# BATTERY_GESTION.net
KiCad netlist of a schematic drawn in Altium Designer
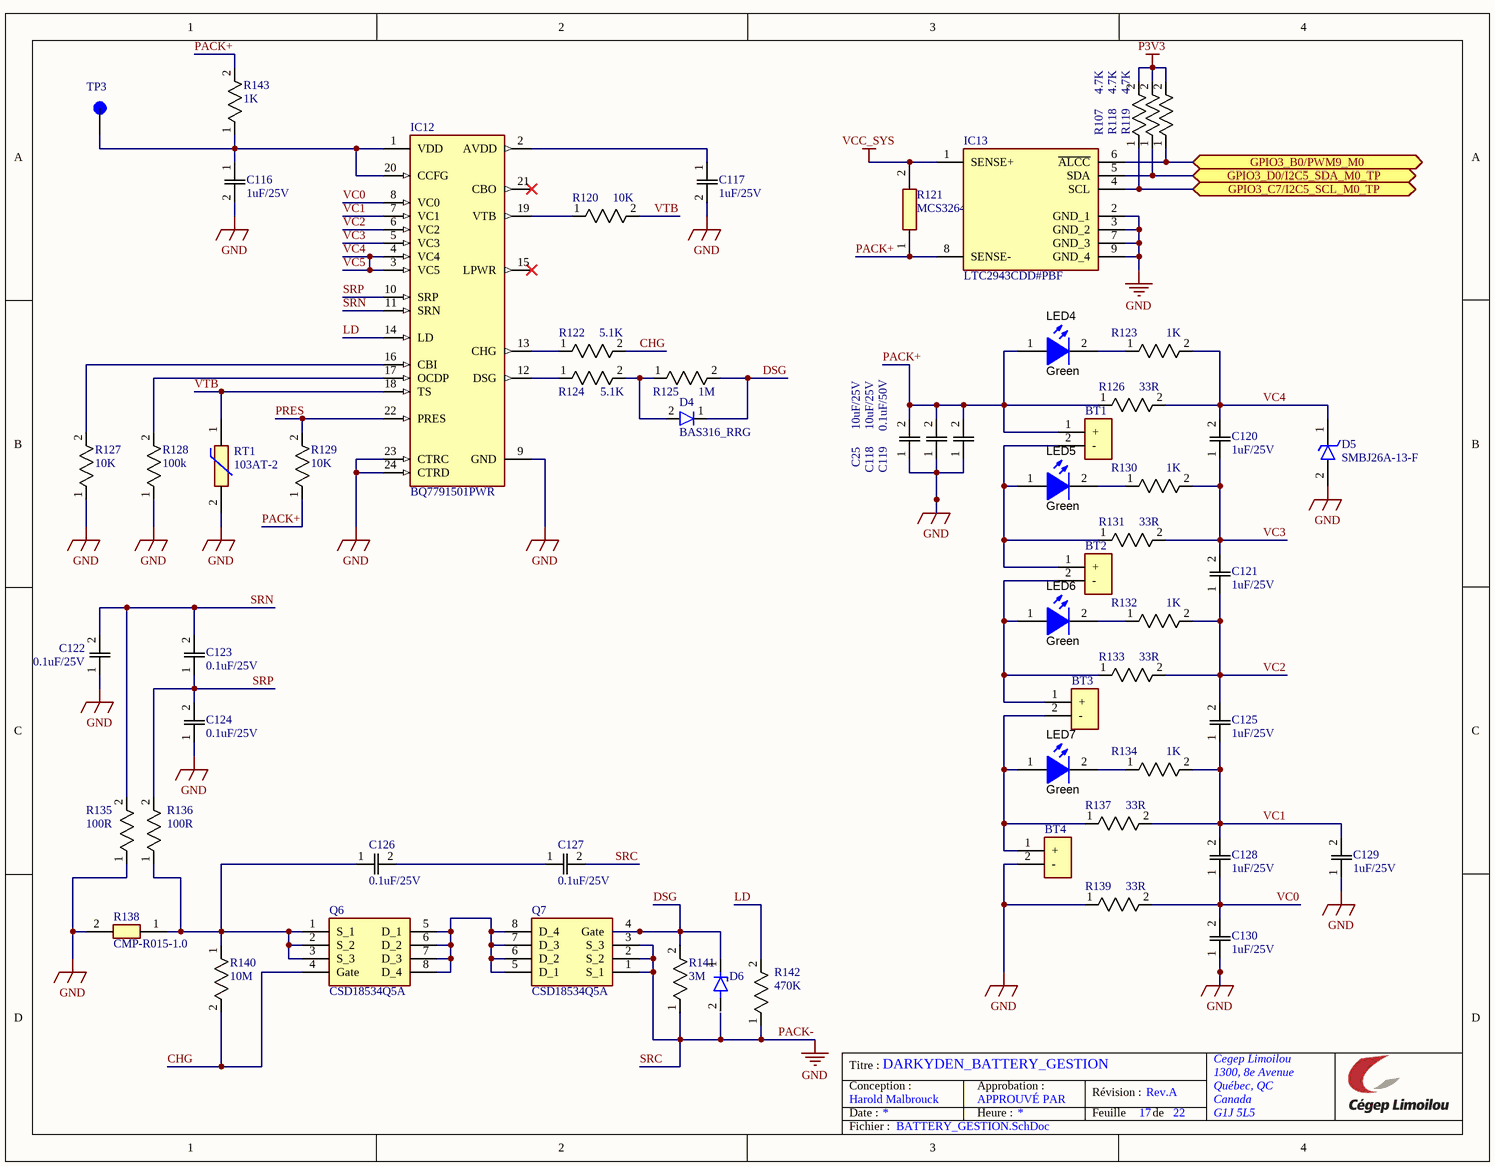
[diagram p0: BATTERY_GESTION.SchDoc]

(export (version "E")
  (design (tool "Eeschema 10.0.6"))
  (components
    (comp (ref "BT1")
      (value "0530480210")
      (footprint "SamacSys:SHDRRA2W35P0X125_1X2_425X550X350P")
      (description "Connector")
      (libsource (lib "SamacSys") (part "Header 1.25MM"))
    )
    (comp (ref "BT2")
      (value "0530480210")
      (footprint "SamacSys:SHDRRA2W35P0X125_1X2_425X550X350P")
      (description "Connector")
      (libsource (lib "SamacSys") (part "Header 1.25MM"))
    )
    (comp (ref "BT3")
      (value "0530480210")
      (footprint "SamacSys:SHDRRA2W35P0X125_1X2_425X550X350P")
      (description "Connector")
      (libsource (lib "SamacSys") (part "Header 1.25MM"))
    )
    (comp (ref "BT4")
      (value "0530480210")
      (footprint "SamacSys:SHDRRA2W35P0X125_1X2_425X550X350P")
      (description "Connector")
      (libsource (lib "SamacSys") (part "Header 1.25MM"))
    )
    (comp (ref "C25")
      (value "10uF/25V")
      (footprint "CAPC220145_88N_KEM")
      (description "10uF / 25 VDC, +85degC, X5R Dielec, +/-10% ¦ KEMET C0805C106K3PACTU 0805")
      (fields
        (field (name "MANUFACTURER") "KEMET")
        (field (name "MANUFACTURER PART NUMBER") "C0805C106K3PACTU")
      )
      (libsource (lib "C0805C106K3PACTU") (part "C0805C106K3PACTU"))
    )
    (comp (ref "C116")
      (value "1uF/25V")
      (footprint "SamacSys:C0805")
      (description "1 µF, 25 V (DC), ±10 %, SMD 0805, X7R, C0805C105K3RAC7800")
      (fields
        (field (name "MANUFACTURER_PART_NUMBER") "C0805C105K3RACTU")
        (field (name "MOUSER PART NUMBER") "80-C0805C105K3R")
      )
      (libsource (lib "SamacSys") (part "C0805C105K3RACTU"))
    )
    (comp (ref "C117")
      (value "1uF/25V")
      (footprint "SamacSys:C0805")
      (description "1 µF, 25 V (DC), ±10 %, SMD 0805, X7R, C0805C105K3RAC7800")
      (fields
        (field (name "MANUFACTURER_PART_NUMBER") "C0805C105K3RACTU")
        (field (name "MOUSER PART NUMBER") "80-C0805C105K3R")
      )
      (libsource (lib "SamacSys") (part "C0805C105K3RACTU"))
    )
    (comp (ref "C118")
      (value "10uF/25V")
      (footprint "CAPC220145_88N_KEM")
      (description "10uF / 25 VDC, +85degC, X5R Dielec, +/-10% ¦ KEMET C0805C106K3PACTU 0805")
      (fields
        (field (name "MANUFACTURER") "KEMET")
        (field (name "MANUFACTURER PART NUMBER") "C0805C106K3PACTU")
      )
      (libsource (lib "C0805C106K3PACTU") (part "C0805C106K3PACTU"))
    )
    (comp (ref "C119")
      (value "0.1uF/50V")
      (footprint "SamacSys:C0805")
      (description "0.1uF/50V X7R 10% 0805 Multilayer Ceramic Capacitors Mlcc Smd/Smt Rohs")
      (fields
        (field (name "MANUFACTURER_PART_NUMBER") "C0805C104K5RACTU")
        (field (name "MOUSER PART NUMBER") "80-C0805C104K5R")
      )
      (libsource (lib "SamacSys") (part "C0805C104K5RACTU"))
    )
    (comp (ref "C120")
      (value "1uF/25V")
      (footprint "SamacSys:C0805")
      (description "1 µF, 25 V (DC), ±10 %, SMD 0805, X7R, C0805C105K3RAC7800")
      (fields
        (field (name "MANUFACTURER_PART_NUMBER") "C0805C105K3RACTU")
        (field (name "MOUSER PART NUMBER") "80-C0805C105K3R")
      )
      (libsource (lib "SamacSys") (part "C0805C105K3RACTU"))
    )
    (comp (ref "C121")
      (value "1uF/25V")
      (footprint "SamacSys:C0805")
      (description "1 µF, 25 V (DC), ±10 %, SMD 0805, X7R, C0805C105K3RAC7800")
      (fields
        (field (name "MANUFACTURER_PART_NUMBER") "C0805C105K3RACTU")
        (field (name "MOUSER PART NUMBER") "80-C0805C105K3R")
      )
      (libsource (lib "SamacSys") (part "C0805C105K3RACTU"))
    )
    (comp (ref "C122")
      (value "0.1uF/25V")
      (footprint "CAPC220145_88N_KEM")
      (description "0.1uF 25V X7R 10% SMD 0805 125C Plastic T/R")
      (fields
        (field (name "MANUFACTURER") "KEMET")
        (field (name "MANUFACTURER PART NUMBER") "C0805C104K3RACTU")
      )
      (libsource (lib "C0805C104K3RACTU") (part "C0805C104K3RACTU"))
    )
    (comp (ref "C123")
      (value "0.1uF/25V")
      (footprint "CAPC220145_88N_KEM")
      (description "0.1uF 25V X7R 10% SMD 0805 125C Plastic T/R")
      (fields
        (field (name "MANUFACTURER") "KEMET")
        (field (name "MANUFACTURER PART NUMBER") "C0805C104K3RACTU")
      )
      (libsource (lib "C0805C104K3RACTU") (part "C0805C104K3RACTU"))
    )
    (comp (ref "C124")
      (value "0.1uF/25V")
      (footprint "CAPC220145_88N_KEM")
      (description "0.1uF 25V X7R 10% SMD 0805 125C Plastic T/R")
      (fields
        (field (name "MANUFACTURER") "KEMET")
        (field (name "MANUFACTURER PART NUMBER") "C0805C104K3RACTU")
      )
      (libsource (lib "C0805C104K3RACTU") (part "C0805C104K3RACTU"))
    )
    (comp (ref "C125")
      (value "1uF/25V")
      (footprint "SamacSys:C0805")
      (description "1 µF, 25 V (DC), ±10 %, SMD 0805, X7R, C0805C105K3RAC7800")
      (fields
        (field (name "MANUFACTURER_PART_NUMBER") "C0805C105K3RACTU")
        (field (name "MOUSER PART NUMBER") "80-C0805C105K3R")
      )
      (libsource (lib "SamacSys") (part "C0805C105K3RACTU"))
    )
    (comp (ref "C126")
      (value "0.1uF/25V")
      (footprint "CAPC220145_88N_KEM")
      (description "0.1uF 25V X7R 10% SMD 0805 125C Plastic T/R")
      (fields
        (field (name "MANUFACTURER") "KEMET")
        (field (name "MANUFACTURER PART NUMBER") "C0805C104K3RACTU")
      )
      (libsource (lib "C0805C104K3RACTU") (part "C0805C104K3RACTU"))
    )
    (comp (ref "C127")
      (value "0.1uF/25V")
      (footprint "CAPC220145_88N_KEM")
      (description "0.1uF 25V X7R 10% SMD 0805 125C Plastic T/R")
      (fields
        (field (name "MANUFACTURER") "KEMET")
        (field (name "MANUFACTURER PART NUMBER") "C0805C104K3RACTU")
      )
      (libsource (lib "C0805C104K3RACTU") (part "C0805C104K3RACTU"))
    )
    (comp (ref "C128")
      (value "1uF/25V")
      (footprint "SamacSys:C0805")
      (description "1 µF, 25 V (DC), ±10 %, SMD 0805, X7R, C0805C105K3RAC7800")
      (fields
        (field (name "MANUFACTURER_PART_NUMBER") "C0805C105K3RACTU")
        (field (name "MOUSER PART NUMBER") "80-C0805C105K3R")
      )
      (libsource (lib "SamacSys") (part "C0805C105K3RACTU"))
    )
    (comp (ref "C129")
      (value "1uF/25V")
      (footprint "SamacSys:C0805")
      (description "1 µF, 25 V (DC), ±10 %, SMD 0805, X7R, C0805C105K3RAC7800")
      (fields
        (field (name "MANUFACTURER_PART_NUMBER") "C0805C105K3RACTU")
        (field (name "MOUSER PART NUMBER") "80-C0805C105K3R")
      )
      (libsource (lib "SamacSys") (part "C0805C105K3RACTU"))
    )
    (comp (ref "C130")
      (value "1uF/25V")
      (footprint "SamacSys:C0805")
      (description "1 µF, 25 V (DC), ±10 %, SMD 0805, X7R, C0805C105K3RAC7800")
      (fields
        (field (name "MANUFACTURER_PART_NUMBER") "C0805C105K3RACTU")
        (field (name "MOUSER PART NUMBER") "80-C0805C105K3R")
      )
      (libsource (lib "SamacSys") (part "C0805C105K3RACTU"))
    )
    (comp (ref "D4")
      (value "BAS316_RRG")
      (footprint "SamacSys:BAS316RRG")
      (description "Rectifier Diode Small Signal Switching 0.25A 4ns 2-Pin SOD-323 T/R")
      (fields
        (field (name "MANUFACTURER_PART_NUMBER") "BAS316 RRG")
        (field (name "MOUSER PART NUMBER") "821-BAS316RRG")
      )
      (libsource (lib "SamacSys") (part "BAS316_RRG"))
    )
    (comp (ref "D5")
      (value "SMBJ26A-13-F")
      (footprint "SamacSys:DIOM5336X250N")
      (description "TVS DIODE 26VWM 42.1VC SMB")
      (fields (field (name "MOUSER PART NUMBER") "621-SMBJ26A-13-F"))
      (libsource (lib "SamacSys") (part "SMBJ26A-13-F"))
    )
    (comp (ref "D6")
      (value "MMSZ5248B-7-F")
      (footprint "SamacSys:SOD3716X115N")
      (description "Zener Diode 18 V 500 mW ±5% Surface Mount SOD-123")
      (libsource (lib "SamacSys") (part "MMSZ5248B-7-F"))
    )
    (comp (ref "IC12")
      (value "BQ7791501PWR")
      (footprint "SamacSys:SOP65P640X120-24N")
      (description "/Polymer 3~5 TSSOP-24 Battery Management ICs ROHS")
      (fields
        (field (name "MOUSER PART NUMBER") "595-BQ7791501PWR")
        (field (name "MANUFACTURER") "Texas Instruments")
      )
      (libsource (lib "SamacSys") (part "BQ7791501PWR"))
    )
    (comp (ref "IC13")
      (value "LTC2943CDD#PBF")
      (footprint "SamacSys:SON50P300X300X80-9N-D")
      (description "LTC2943 - Multicell Battery Gas Gauge with Temperature, Voltage and Current Measurement")
      (fields
        (field (name "MOUSER PART NUMBER") "584-LTC2943CDD#PBF")
        (field (name "MANUFACTURER") "Analog Devices / Linear Technology")
      )
      (libsource (lib "SamacSys") (part "LTC2943CDD#PBF"))
    )
    (comp (ref "LED4")
      (value "Green")
      (footprint "LED_LTST-C190")
      (description "LED, Green, SMD")
      (fields (field (name "MANUFACTURER") "Lite-On") (field (name "PARTNUMBER") "LTST-C190GKT"))
      (libsource (lib "PD_BQ_Ref_Design") (part "LED_Gr_SMD"))
    )
    (comp (ref "LED5")
      (value "Green")
      (footprint "LED_LTST-C190")
      (description "LED, Green, SMD")
      (fields (field (name "MANUFACTURER") "Lite-On") (field (name "PARTNUMBER") "LTST-C190GKT"))
      (libsource (lib "PD_BQ_Ref_Design") (part "LED_Gr_SMD"))
    )
    (comp (ref "LED6")
      (value "Green")
      (footprint "LED_LTST-C190")
      (description "LED, Green, SMD")
      (fields (field (name "MANUFACTURER") "Lite-On") (field (name "PARTNUMBER") "LTST-C190GKT"))
      (libsource (lib "PD_BQ_Ref_Design") (part "LED_Gr_SMD"))
    )
    (comp (ref "LED7")
      (value "Green")
      (footprint "LED_LTST-C190")
      (description "LED, Green, SMD")
      (fields (field (name "MANUFACTURER") "Lite-On") (field (name "PARTNUMBER") "LTST-C190GKT"))
      (libsource (lib "PD_BQ_Ref_Design") (part "LED_Gr_SMD"))
    )
    (comp (ref "Q6")
      (value "CSD18534Q5A")
      (footprint "SamacSys:Q5A")
      (description "MOSFET N-Channel 60 V 13A (Ta), 50A (Tc) 3.1W (Ta), 77W (Tc) Surface Mount 8-VSONP (5x6)")
      (fields (field (name "MOUSER PART NUMBER") "595-CSD18534Q5A"))
      (libsource (lib "SamacSys") (part "CSD18534Q5A"))
    )
    (comp (ref "Q7")
      (value "CSD18534Q5A")
      (footprint "SamacSys:Q5A")
      (description "MOSFET N-Channel 60 V 13A (Ta), 50A (Tc) 3.1W (Ta), 77W (Tc) Surface Mount 8-VSONP (5x6)")
      (fields (field (name "MOUSER PART NUMBER") "595-CSD18534Q5A"))
      (libsource (lib "") (part "CSD18534Q5A_1"))
    )
    (comp (ref "R107")
      (value "4.7K")
      (footprint "RC0603N_PAN")
      (description "Res Thin Film 0603 4.7K Ohm 0.1% 0.1W ±25ppm/°C Molded SMD Punched Carrier T/R")
      (fields
        (field (name "MANUFACTURER") "Panasonic")
        (field (name "MANUFACTURER PART NUMBER") "ERA-3AEB472V")
      )
      (libsource (lib "ERA-3AEB472V") (part "ERA-3AEB472V"))
    )
    (comp (ref "R118")
      (value "4.7K")
      (footprint "RC0603N_PAN")
      (description "Res Thin Film 0603 4.7K Ohm 0.1% 0.1W ±25ppm/°C Molded SMD Punched Carrier T/R")
      (fields
        (field (name "MANUFACTURER") "Panasonic")
        (field (name "MANUFACTURER PART NUMBER") "ERA-3AEB472V")
      )
      (libsource (lib "ERA-3AEB472V") (part "ERA-3AEB472V"))
    )
    (comp (ref "R119")
      (value "4.7K")
      (footprint "RC0603N_PAN")
      (description "Res Thin Film 0603 4.7K Ohm 0.1% 0.1W ±25ppm/°C Molded SMD Punched Carrier T/R")
      (fields
        (field (name "MANUFACTURER") "Panasonic")
        (field (name "MANUFACTURER PART NUMBER") "ERA-3AEB472V")
      )
      (libsource (lib "ERA-3AEB472V") (part "ERA-3AEB472V"))
    )
    (comp (ref "R120")
      (value "10K")
      (footprint "SamacSys:ERJ3EKF1000V")
      (description "10K Ohm 5% Res Thick Film 0603  0.1W(1/10W) ±200ppm/C Pad SMD Automotive T/R")
      (fields
        (field (name "MANUFACTURER_PART_NUMBER") "ERJ-3GEYJ103V")
        (field (name "MOUSER PART NUMBER") "667-ERJ-3GEYJ103V")
      )
      (libsource (lib "SamacSys") (part "ERJ-3GEYJ103V"))
    )
    (comp (ref "R121")
      (value "MCS3264R010FER")
      (footprint "SamacSys:RESC6432X62N")
      (description "Res Metal Alloy 2512 0.01 Ohm 1% 2W 50ppm/ C Molded SMD T/R")
      (fields (field (name "MOUSER PART NUMBER") "588-MCS3264R010FER") (field (name "MANUFACTURER") "Ohmite"))
      (libsource (lib "SamacSys") (part "MCS3264R010FER"))
    )
    (comp (ref "R122")
      (value "5.1K")
      (footprint "SamacSys:ERA3AEB101V")
      (description "5.1K Ohm 0.05% 0.1W ±10ppm/°C Molded Res Thin Film 0603 SMD Punched Carrier T/R")
      (fields
        (field (name "MANUFACTURER_PART_NUMBER") "ERA-3ARW512V")
        (field (name "MOUSER PART NUMBER") "667-ERA-3ARW512V")
      )
      (libsource (lib "SamacSys") (part "ERA-3ARW512V"))
    )
    (comp (ref "R123")
      (value "1K")
      (footprint "SamacSys:RESC1608X55N")
      (description "1K Ohm 1% 1/10W Res Thick Film 0603 ±100ppm/°C Molded SMD Punched Carrier T/R")
      (fields
        (field (name "MANUFACTURER_PART_NUMBER") "ERJ-3EKF1001V")
        (field (name "MOUSER PART NUMBER") "667-ERJ-3EKF1001V")
      )
      (libsource (lib "SamacSys") (part "ERJ-3EKF1001V"))
    )
    (comp (ref "R124")
      (value "5.1K")
      (footprint "SamacSys:ERA3AEB101V")
      (description "5.1K Ohm 0.05% 0.1W ±10ppm/°C Molded Res Thin Film 0603 SMD Punched Carrier T/R")
      (fields
        (field (name "MANUFACTURER_PART_NUMBER") "ERA-3ARW512V")
        (field (name "MOUSER PART NUMBER") "667-ERA-3ARW512V")
      )
      (libsource (lib "SamacSys") (part "ERA-3ARW512V"))
    )
    (comp (ref "R125")
      (value "1M")
      (footprint "SamacSys:ERJ3EKF1000V")
      (description "1M Ohm Res Thick Film 0603 5% 0.1W(1/10W) +/-200ppm/ßC SMD Automotive T/R")
      (fields
        (field (name "MANUFACTURER_PART_NUMBER") "ERJ-3GEYJ105V")
        (field (name "MOUSER PART NUMBER") "667-ERJ-3GEYJ105V")
      )
      (libsource (lib "SamacSys") (part "ERJ-3GEYJ105V"))
    )
    (comp (ref "R126")
      (value "33R")
      (footprint "RC0603N_PAN")
      (description "Res Thick Film 0603 33 Ohm 1% 0.1W ±100ppm/°C Molded SMD Punched Carrier T/R")
      (fields
        (field (name "MANUFACTURER") "Panasonic")
        (field (name "MANUFACTURER PART NUMBER") "ERJ-3EKF33R0V")
      )
      (libsource (lib "ERJ-3EKF33R0V") (part "ERJ-3EKF33R0V"))
    )
    (comp (ref "R127")
      (value "10K")
      (footprint "SamacSys:ERJ3EKF1000V")
      (description "10K Ohm 5% Res Thick Film 0603  0.1W(1/10W) ±200ppm/C Pad SMD Automotive T/R")
      (fields
        (field (name "MANUFACTURER_PART_NUMBER") "ERJ-3GEYJ103V")
        (field (name "MOUSER PART NUMBER") "667-ERJ-3GEYJ103V")
      )
      (libsource (lib "SamacSys") (part "ERJ-3GEYJ103V"))
    )
    (comp (ref "R128")
      (value "100k")
      (footprint "SamacSys:ERJ3EKF1000V")
      (description "100K Ohm 5%  Res Thick Film 0603 1/10W +/-200ppm/ßC Molded SMD Punched Carrier T/R")
      (fields
        (field (name "MANUFACTURER_PART_NUMBER") "ERJ-3GEYJ104V")
        (field (name "MOUSER PART NUMBER") "667-ERJ-3GEYJ104V")
      )
      (libsource (lib "SamacSys") (part "ERJ-3GEYJ104V"))
    )
    (comp (ref "R129")
      (value "10K")
      (footprint "SamacSys:ERJ3EKF1000V")
      (description "10K Ohm 5% Res Thick Film 0603  0.1W(1/10W) ±200ppm/C Pad SMD Automotive T/R")
      (fields
        (field (name "MANUFACTURER_PART_NUMBER") "ERJ-3GEYJ103V")
        (field (name "MOUSER PART NUMBER") "667-ERJ-3GEYJ103V")
      )
      (libsource (lib "SamacSys") (part "ERJ-3GEYJ103V"))
    )
    (comp (ref "R130")
      (value "1K")
      (footprint "SamacSys:RESC1608X55N")
      (description "1K Ohm 1% 1/10W Res Thick Film 0603 ±100ppm/°C Molded SMD Punched Carrier T/R")
      (fields
        (field (name "MANUFACTURER_PART_NUMBER") "ERJ-3EKF1001V")
        (field (name "MOUSER PART NUMBER") "667-ERJ-3EKF1001V")
      )
      (libsource (lib "SamacSys") (part "ERJ-3EKF1001V"))
    )
    (comp (ref "R131")
      (value "33R")
      (footprint "RC0603N_PAN")
      (description "Res Thick Film 0603 33 Ohm 1% 0.1W ±100ppm/°C Molded SMD Punched Carrier T/R")
      (fields
        (field (name "MANUFACTURER") "Panasonic")
        (field (name "MANUFACTURER PART NUMBER") "ERJ-3EKF33R0V")
      )
      (libsource (lib "ERJ-3EKF33R0V") (part "ERJ-3EKF33R0V"))
    )
    (comp (ref "R132")
      (value "1K")
      (footprint "SamacSys:RESC1608X55N")
      (description "1K Ohm 1% 1/10W Res Thick Film 0603 ±100ppm/°C Molded SMD Punched Carrier T/R")
      (fields
        (field (name "MANUFACTURER_PART_NUMBER") "ERJ-3EKF1001V")
        (field (name "MOUSER PART NUMBER") "667-ERJ-3EKF1001V")
      )
      (libsource (lib "SamacSys") (part "ERJ-3EKF1001V"))
    )
    (comp (ref "R133")
      (value "33R")
      (footprint "RC0603N_PAN")
      (description "Res Thick Film 0603 33 Ohm 1% 0.1W ±100ppm/°C Molded SMD Punched Carrier T/R")
      (fields
        (field (name "MANUFACTURER") "Panasonic")
        (field (name "MANUFACTURER PART NUMBER") "ERJ-3EKF33R0V")
      )
      (libsource (lib "ERJ-3EKF33R0V") (part "ERJ-3EKF33R0V"))
    )
    (comp (ref "R134")
      (value "1K")
      (footprint "SamacSys:RESC1608X55N")
      (description "1K Ohm 1% 1/10W Res Thick Film 0603 ±100ppm/°C Molded SMD Punched Carrier T/R")
      (fields
        (field (name "MANUFACTURER_PART_NUMBER") "ERJ-3EKF1001V")
        (field (name "MOUSER PART NUMBER") "667-ERJ-3EKF1001V")
      )
      (libsource (lib "SamacSys") (part "ERJ-3EKF1001V"))
    )
    (comp (ref "R135")
      (value "100R")
      (footprint "SamacSys:RESC1608X55N")
      (description "100 Ohm 1% 1/10W 0603 ±100ppm/°C Molded SMD Punched Carrier T/R")
      (fields
        (field (name "MANUFACTURER_PART_NUMBER") "ERJ-3EKF1000V")
        (field (name "MOUSER PART NUMBER") "667-ERJ-3EKF1000V")
      )
      (libsource (lib "SamacSys") (part "ERJ-3EKF1000V"))
    )
    (comp (ref "R136")
      (value "100R")
      (footprint "SamacSys:RESC1608X55N")
      (description "100 Ohm 1% 1/10W 0603 ±100ppm/°C Molded SMD Punched Carrier T/R")
      (fields
        (field (name "MANUFACTURER_PART_NUMBER") "ERJ-3EKF1000V")
        (field (name "MOUSER PART NUMBER") "667-ERJ-3EKF1000V")
      )
      (libsource (lib "SamacSys") (part "ERJ-3EKF1000V"))
    )
    (comp (ref "R137")
      (value "33R")
      (footprint "RC0603N_PAN")
      (description "Res Thick Film 0603 33 Ohm 1% 0.1W ±100ppm/°C Molded SMD Punched Carrier T/R")
      (fields
        (field (name "MANUFACTURER") "Panasonic")
        (field (name "MANUFACTURER PART NUMBER") "ERJ-3EKF33R0V")
      )
      (libsource (lib "ERJ-3EKF33R0V") (part "ERJ-3EKF33R0V"))
    )
    (comp (ref "R138")
      (value "CMP-R015-1.0")
      (footprint "SamacSys:RESC5025X70N")
      (description "Package 2010")
      (fields
        (field (name "MANUFACTURER_PART_NUMBER") "CRCW20100000Z0EFHP")
        (field (name "MOUSER PART NUMBER") "71-CRCW20100000Z0EFH")
      )
      (libsource (lib "SamacSys") (part "Resistor 2010"))
    )
    (comp (ref "R139")
      (value "33R")
      (footprint "RC0603N_PAN")
      (description "Res Thick Film 0603 33 Ohm 1% 0.1W ±100ppm/°C Molded SMD Punched Carrier T/R")
      (fields
        (field (name "MANUFACTURER") "Panasonic")
        (field (name "MANUFACTURER PART NUMBER") "ERJ-3EKF33R0V")
      )
      (libsource (lib "ERJ-3EKF33R0V") (part "ERJ-3EKF33R0V"))
    )
    (comp (ref "R140")
      (value "10M")
      (footprint "SamacSys:ERJS03J155V")
      (description "10Mohm 5%  SMD 0603   Anti-Sulfur AEC-Q200")
      (fields
        (field (name "MANUFACTURER_PART_NUMBER") "ERJ-U03J106V")
        (field (name "MOUSER PART NUMBER") "667-ERJ-U03J106V")
      )
      (libsource (lib "SamacSys") (part "ERJ-U03J106V"))
    )
    (comp (ref "R141")
      (value "3M")
      (footprint "SamacSys:ERJ3EKF1000V")
      (description "3M Ohm 5% 1/10W Res Thick Film 0603 -400ppm/ to 150¦")
      (fields
        (field (name "MANUFACTURER_PART_NUMBER") "ERJ-3GEYJ305V")
        (field (name "MOUSER PART NUMBER") "667-ERJ-3GEYJ305V")
      )
      (libsource (lib "SamacSys") (part "ERJ-3GEYJ305V"))
    )
    (comp (ref "R142")
      (value "470K")
      (footprint "SamacSys:RESC1608X55N")
      (description "470K Ohm 1% 0.1W  Res Thick Film 0603 ±100ppm/°C Molded SMD Punched Carrier T/R")
      (fields
        (field (name "MANUFACTURER_PART_NUMBER") "ERJ-3EKF4703V")
        (field (name "MOUSER PART NUMBER") "667-ERJ-3EKF4703V")
      )
      (libsource (lib "SamacSys") (part "ERJ-3EKF4703V"))
    )
    (comp (ref "R143")
      (value "1K")
      (footprint "SamacSys:RESC1608X55N")
      (description "1K Ohm 1% 1/10W Res Thick Film 0603 ±100ppm/°C Molded SMD Punched Carrier T/R")
      (fields
        (field (name "MANUFACTURER_PART_NUMBER") "ERJ-3EKF1001V")
        (field (name "MOUSER PART NUMBER") "667-ERJ-3EKF1001V")
      )
      (libsource (lib "SamacSys") (part "ERJ-3EKF1001V"))
    )
    (comp (ref "RT1")
      (value "103AT-2")
      (footprint "SamacSys:103AT2")
      (description "NTC Thermistor 10k Bead")
      (fields (field (name "MOUSER PART NUMBER") "954-103AT-2"))
      (libsource (lib "SamacSys") (part "103AT-2"))
    )
    (comp (ref "TP3")
      (value "CHARGE_TP")
      (footprint "KEYSTONE_5006")
      (description "Test Point Compact THM PC .350 L .125 OD Heat Resistant Nylon 46 Black ¦ Keystone Electronics 5006")
      (fields (field (name "MF") "Keystone Electronics Corp.") (field (name "MP") "5006"))
      (libsource (lib "test_point") (part "5006"))
    )
  )
  (nets
    (net (code "1") (name "/CHG") (class "Default")
      (node (ref "Q6") (pin "4") (pinfunction "Gate_4") (pintype "passive"))
      (node (ref "R122") (pin "2") (pinfunction "2_2") (pintype "passive"))
      (node (ref "R140") (pin "2") (pinfunction "2_2") (pintype "passive"))
    )
    (net (code "2") (name "/DSG") (class "Default")
      (node (ref "D4") (pin "1") (pinfunction "K_1") (pintype "passive"))
      (node (ref "D6") (pin "1") (pinfunction "K_1") (pintype "passive"))
      (node (ref "Q7") (pin "4") (pinfunction "Gate_4") (pintype "passive"))
      (node (ref "R125") (pin "2") (pinfunction "2_2") (pintype "passive"))
      (node (ref "R141") (pin "2") (pinfunction "2_2") (pintype "passive"))
    )
    (net (code "3") (name "/GPIO3_B0{slash}PWM9_M0") (class "Default")
      (node (ref "IC13") (pin "6") (pinfunction "~{ALCC}_6") (pintype "passive"))
      (node (ref "R119") (pin "1") (pinfunction "1_1") (pintype "passive"))
    )
    (net (code "4") (name "/GPIO3_C7{slash}I2C5_SCL_M0_TP") (class "Default")
      (node (ref "IC13") (pin "4") (pinfunction "SCL_4") (pintype "passive"))
      (node (ref "R107") (pin "1") (pinfunction "1_1") (pintype "passive"))
    )
    (net (code "5") (name "/GPIO3_D0{slash}I2C5_SDA_M0_TP") (class "Default")
      (node (ref "IC13") (pin "5") (pinfunction "SDA_5") (pintype "passive"))
      (node (ref "R118") (pin "1") (pinfunction "1_1") (pintype "passive"))
    )
    (net (code "6") (name "/LD") (class "Default")
      (node (ref "IC12") (pin "14") (pinfunction "LD_14") (pintype "input"))
      (node (ref "R142") (pin "2") (pinfunction "2_2") (pintype "passive"))
    )
    (net (code "7") (name "/PACK+") (class "Default")
      (node (ref "BT1") (pin "1") (pinfunction "+_1") (pintype "passive"))
      (node (ref "C118") (pin "2") (pinfunction "2_2") (pintype "passive"))
      (node (ref "C119") (pin "2") (pinfunction "2_2") (pintype "passive"))
      (node (ref "C25") (pin "2") (pinfunction "2_2") (pintype "passive"))
      (node (ref "IC13") (pin "8") (pinfunction "SENSE-_8") (pintype "passive"))
      (node (ref "LED4") (pin "1") (pinfunction "A_1") (pintype "passive"))
      (node (ref "R121") (pin "1") (pinfunction "1_1") (pintype "passive"))
      (node (ref "R126") (pin "1") (pinfunction "1_1") (pintype "passive"))
      (node (ref "R129") (pin "1") (pinfunction "1_1") (pintype "passive"))
      (node (ref "R143") (pin "2") (pinfunction "2_2") (pintype "passive"))
    )
    (net (code "8") (name "/PRES") (class "Default")
      (node (ref "IC12") (pin "22") (pinfunction "PRES_22") (pintype "input"))
      (node (ref "R129") (pin "2") (pinfunction "2_2") (pintype "passive"))
    )
    (net (code "9") (name "/SRN") (class "Default")
      (node (ref "C122") (pin "2") (pinfunction "2_2") (pintype "passive"))
      (node (ref "C123") (pin "2") (pinfunction "2_2") (pintype "passive"))
      (node (ref "IC12") (pin "11") (pinfunction "SRN_11") (pintype "input"))
      (node (ref "R135") (pin "2") (pinfunction "2_2") (pintype "passive"))
    )
    (net (code "10") (name "/SRP") (class "Default")
      (node (ref "C123") (pin "1") (pinfunction "1_1") (pintype "passive"))
      (node (ref "C124") (pin "2") (pinfunction "2_2") (pintype "passive"))
      (node (ref "IC12") (pin "10") (pinfunction "SRP_10") (pintype "input"))
      (node (ref "R136") (pin "2") (pinfunction "2_2") (pintype "passive"))
    )
    (net (code "11") (name "/VC0") (class "Default")
      (node (ref "C128") (pin "1") (pinfunction "1_1") (pintype "passive"))
      (node (ref "C130") (pin "2") (pinfunction "2_2") (pintype "passive"))
      (node (ref "IC12") (pin "8") (pinfunction "VC0_8") (pintype "input"))
      (node (ref "R139") (pin "2") (pinfunction "2_2") (pintype "passive"))
    )
    (net (code "12") (name "/VC1") (class "Default")
      (node (ref "C125") (pin "1") (pinfunction "1_1") (pintype "passive"))
      (node (ref "C128") (pin "2") (pinfunction "2_2") (pintype "passive"))
      (node (ref "C129") (pin "2") (pinfunction "2_2") (pintype "passive"))
      (node (ref "IC12") (pin "7") (pinfunction "VC1_7") (pintype "input"))
      (node (ref "R134") (pin "2") (pinfunction "2_2") (pintype "passive"))
      (node (ref "R137") (pin "2") (pinfunction "2_2") (pintype "passive"))
    )
    (net (code "13") (name "/VC2") (class "Default")
      (node (ref "C121") (pin "1") (pinfunction "1_1") (pintype "passive"))
      (node (ref "C125") (pin "2") (pinfunction "2_2") (pintype "passive"))
      (node (ref "IC12") (pin "6") (pinfunction "VC2_6") (pintype "input"))
      (node (ref "R132") (pin "2") (pinfunction "2_2") (pintype "passive"))
      (node (ref "R133") (pin "2") (pinfunction "2_2") (pintype "passive"))
    )
    (net (code "14") (name "/VC3") (class "Default")
      (node (ref "C120") (pin "1") (pinfunction "1_1") (pintype "passive"))
      (node (ref "C121") (pin "2") (pinfunction "2_2") (pintype "passive"))
      (node (ref "IC12") (pin "5") (pinfunction "VC3_5") (pintype "input"))
      (node (ref "R130") (pin "2") (pinfunction "2_2") (pintype "passive"))
      (node (ref "R131") (pin "2") (pinfunction "2_2") (pintype "passive"))
    )
    (net (code "15") (name "/VC4") (class "Default")
      (node (ref "C120") (pin "2") (pinfunction "2_2") (pintype "passive"))
      (node (ref "D5") (pin "1") (pinfunction "K_1") (pintype "passive"))
      (node (ref "IC12") (pin "3") (pinfunction "VC5_3") (pintype "input"))
      (node (ref "IC12") (pin "4") (pinfunction "VC4_4") (pintype "input"))
      (node (ref "R123") (pin "2") (pinfunction "2_2") (pintype "passive"))
      (node (ref "R126") (pin "2") (pinfunction "2_2") (pintype "passive"))
    )
    (net (code "16") (name "/VTB") (class "Default")
      (node (ref "IC12") (pin "18") (pinfunction "TS_18") (pintype "input"))
      (node (ref "R120") (pin "2") (pinfunction "2_2") (pintype "passive"))
      (node (ref "RT1") (pin "1") (pinfunction "1_1") (pintype "passive"))
    )
    (net (code "17") (name "GND") (class "Default")
      (node (ref "BT4") (pin "2") (pinfunction "-_2") (pintype "passive"))
      (node (ref "C116") (pin "2") (pinfunction "2_2") (pintype "passive"))
      (node (ref "C117") (pin "2") (pinfunction "2_2") (pintype "passive"))
      (node (ref "C118") (pin "1") (pinfunction "1_1") (pintype "passive"))
      (node (ref "C119") (pin "1") (pinfunction "1_1") (pintype "passive"))
      (node (ref "C122") (pin "1") (pinfunction "1_1") (pintype "passive"))
      (node (ref "C124") (pin "1") (pinfunction "1_1") (pintype "passive"))
      (node (ref "C127") (pin "2") (pinfunction "2_2") (pintype "passive"))
      (node (ref "C129") (pin "1") (pinfunction "1_1") (pintype "passive"))
      (node (ref "C130") (pin "1") (pinfunction "1_1") (pintype "passive"))
      (node (ref "C25") (pin "1") (pinfunction "1_1") (pintype "passive"))
      (node (ref "D5") (pin "2") (pinfunction "A_2") (pintype "passive"))
      (node (ref "IC12") (pin "23") (pinfunction "CTRC_23") (pintype "input"))
      (node (ref "IC12") (pin "24") (pinfunction "CTRD_24") (pintype "input"))
      (node (ref "IC12") (pin "9") (pinfunction "GND_9") (pintype "passive"))
      (node (ref "IC13") (pin "2") (pinfunction "GND_1_2") (pintype "passive"))
      (node (ref "IC13") (pin "3") (pinfunction "GND_2_3") (pintype "passive"))
      (node (ref "IC13") (pin "7") (pinfunction "GND_3_7") (pintype "passive"))
      (node (ref "IC13") (pin "9") (pinfunction "GND_4_9") (pintype "passive"))
      (node (ref "Q7") (pin "1") (pinfunction "S_1_1") (pintype "passive"))
      (node (ref "Q7") (pin "2") (pinfunction "S_2_2") (pintype "passive"))
      (node (ref "Q7") (pin "3") (pinfunction "S_3_3") (pintype "passive"))
      (node (ref "R127") (pin "1") (pinfunction "1_1") (pintype "passive"))
      (node (ref "R128") (pin "1") (pinfunction "1_1") (pintype "passive"))
      (node (ref "R135") (pin "1") (pinfunction "1_1") (pintype "passive"))
      (node (ref "R138") (pin "2") (pinfunction "2_2") (pintype "passive"))
      (node (ref "R139") (pin "1") (pinfunction "1_1") (pintype "passive"))
      (node (ref "R141") (pin "1") (pinfunction "1_1") (pintype "passive"))
      (node (ref "R142") (pin "1") (pinfunction "1_1") (pintype "passive"))
      (node (ref "RT1") (pin "2") (pinfunction "2_2") (pintype "passive"))
    )
    (net (code "18") (name "Net-(BT1--)") (class "Default")
      (node (ref "BT1") (pin "2") (pinfunction "-_2") (pintype "passive"))
      (node (ref "BT2") (pin "1") (pinfunction "+_1") (pintype "passive"))
      (node (ref "LED5") (pin "1") (pinfunction "A_1") (pintype "passive"))
      (node (ref "R131") (pin "1") (pinfunction "1_1") (pintype "passive"))
    )
    (net (code "19") (name "Net-(BT2--)") (class "Default")
      (node (ref "BT2") (pin "2") (pinfunction "-_2") (pintype "passive"))
      (node (ref "BT3") (pin "1") (pinfunction "+_1") (pintype "passive"))
      (node (ref "LED6") (pin "1") (pinfunction "A_1") (pintype "passive"))
      (node (ref "R133") (pin "1") (pinfunction "1_1") (pintype "passive"))
    )
    (net (code "20") (name "Net-(BT3--)") (class "Default")
      (node (ref "BT3") (pin "2") (pinfunction "-_2") (pintype "passive"))
      (node (ref "BT4") (pin "1") (pinfunction "+_1") (pintype "passive"))
      (node (ref "LED7") (pin "1") (pinfunction "A_1") (pintype "passive"))
      (node (ref "R137") (pin "1") (pinfunction "1_1") (pintype "passive"))
    )
    (net (code "21") (name "Net-(C126-Pad2)") (class "Default")
      (node (ref "C126") (pin "2") (pinfunction "2_2") (pintype "passive"))
      (node (ref "C127") (pin "1") (pinfunction "1_1") (pintype "passive"))
    )
    (net (code "22") (name "Net-(D4-A)") (class "Default")
      (node (ref "D4") (pin "2") (pinfunction "A_2") (pintype "passive"))
      (node (ref "R124") (pin "2") (pinfunction "2_2") (pintype "passive"))
      (node (ref "R125") (pin "1") (pinfunction "1_1") (pintype "passive"))
    )
    (net (code "23") (name "Net-(IC12-AVDD)") (class "Default")
      (node (ref "C117") (pin "1") (pinfunction "1_1") (pintype "passive"))
      (node (ref "IC12") (pin "2") (pinfunction "AVDD_2") (pintype "output"))
    )
    (net (code "24") (name "Net-(IC12-CBI)") (class "Default")
      (node (ref "IC12") (pin "16") (pinfunction "CBI_16") (pintype "input"))
      (node (ref "R127") (pin "2") (pinfunction "2_2") (pintype "passive"))
    )
    (net (code "25") (name "Net-(IC12-CCFG)") (class "Default")
      (node (ref "C116") (pin "1") (pinfunction "1_1") (pintype "passive"))
      (node (ref "IC12") (pin "1") (pinfunction "VDD_1") (pintype "power_in"))
      (node (ref "IC12") (pin "20") (pinfunction "CCFG_20") (pintype "input"))
      (node (ref "R143") (pin "1") (pinfunction "1_1") (pintype "passive"))
      (node (ref "TP3") (pin "TP") (pinfunction "TP_TP") (pintype "passive"))
    )
    (net (code "26") (name "Net-(IC12-CHG)") (class "Default")
      (node (ref "IC12") (pin "13") (pinfunction "CHG_13") (pintype "output"))
      (node (ref "R122") (pin "1") (pinfunction "1_1") (pintype "passive"))
    )
    (net (code "27") (name "Net-(IC12-DSG)") (class "Default")
      (node (ref "IC12") (pin "12") (pinfunction "DSG_12") (pintype "output"))
      (node (ref "R124") (pin "1") (pinfunction "1_1") (pintype "passive"))
    )
    (net (code "28") (name "Net-(IC12-OCDP)") (class "Default")
      (node (ref "IC12") (pin "17") (pinfunction "OCDP_17") (pintype "input"))
      (node (ref "R128") (pin "2") (pinfunction "2_2") (pintype "passive"))
    )
    (net (code "29") (name "Net-(IC12-VTB)") (class "Default")
      (node (ref "IC12") (pin "19") (pinfunction "VTB_19") (pintype "output"))
      (node (ref "R120") (pin "1") (pinfunction "1_1") (pintype "passive"))
    )
    (net (code "30") (name "Net-(LED4-K)") (class "Default")
      (node (ref "LED4") (pin "2") (pinfunction "K_2") (pintype "passive"))
      (node (ref "R123") (pin "1") (pinfunction "1_1") (pintype "passive"))
    )
    (net (code "31") (name "Net-(LED5-K)") (class "Default")
      (node (ref "LED5") (pin "2") (pinfunction "K_2") (pintype "passive"))
      (node (ref "R130") (pin "1") (pinfunction "1_1") (pintype "passive"))
    )
    (net (code "32") (name "Net-(LED6-K)") (class "Default")
      (node (ref "LED6") (pin "2") (pinfunction "K_2") (pintype "passive"))
      (node (ref "R132") (pin "1") (pinfunction "1_1") (pintype "passive"))
    )
    (net (code "33") (name "Net-(LED7-K)") (class "Default")
      (node (ref "LED7") (pin "2") (pinfunction "K_2") (pintype "passive"))
      (node (ref "R134") (pin "1") (pinfunction "1_1") (pintype "passive"))
    )
    (net (code "34") (name "Net-(Q6-D_1)") (class "Default")
      (node (ref "Q6") (pin "5") (pinfunction "D_1_5") (pintype "passive"))
      (node (ref "Q6") (pin "6") (pinfunction "D_2_6") (pintype "passive"))
      (node (ref "Q6") (pin "7") (pinfunction "D_3_7") (pintype "passive"))
      (node (ref "Q6") (pin "8") (pinfunction "D_4_8") (pintype "passive"))
      (node (ref "Q7") (pin "5") (pinfunction "D_1_5") (pintype "passive"))
      (node (ref "Q7") (pin "6") (pinfunction "D_2_6") (pintype "passive"))
      (node (ref "Q7") (pin "7") (pinfunction "D_3_7") (pintype "passive"))
      (node (ref "Q7") (pin "8") (pinfunction "D_4_8") (pintype "passive"))
    )
    (net (code "35") (name "Net-(Q6-S_1)") (class "Default")
      (node (ref "C126") (pin "1") (pinfunction "1_1") (pintype "passive"))
      (node (ref "Q6") (pin "1") (pinfunction "S_1_1") (pintype "passive"))
      (node (ref "Q6") (pin "2") (pinfunction "S_2_2") (pintype "passive"))
      (node (ref "Q6") (pin "3") (pinfunction "S_3_3") (pintype "passive"))
      (node (ref "R136") (pin "1") (pinfunction "1_1") (pintype "passive"))
      (node (ref "R138") (pin "1") (pinfunction "1_1") (pintype "passive"))
      (node (ref "R140") (pin "1") (pinfunction "1_1") (pintype "passive"))
    )
    (net (code "36") (name "P3V3") (class "Default")
      (node (ref "R107") (pin "2") (pinfunction "2_2") (pintype "passive"))
      (node (ref "R118") (pin "2") (pinfunction "2_2") (pintype "passive"))
      (node (ref "R119") (pin "2") (pinfunction "2_2") (pintype "passive"))
    )
    (net (code "37") (name "VCC_SYS") (class "Default")
      (node (ref "IC13") (pin "1") (pinfunction "SENSE+_1") (pintype "passive"))
      (node (ref "R121") (pin "2") (pinfunction "2_2") (pintype "passive"))
    )
    (net (code "38") (name "unconnected-(D6-A-Pad2)") (class "Default")
      (node (ref "D6") (pin "2") (pinfunction "A_2") (pintype "passive"))
    )
    (net (code "39") (name "unconnected-(IC12-CBO-Pad21)") (class "Default")
      (node (ref "IC12") (pin "21") (pinfunction "CBO_21") (pintype "output+no_connect"))
    )
    (net (code "40") (name "unconnected-(IC12-LPWR-Pad15)") (class "Default")
      (node (ref "IC12") (pin "15") (pinfunction "LPWR_15") (pintype "output+no_connect"))
    )
  )
)
